# simulation.net
KiCad netlist of a schematic drawn in Altium Designer
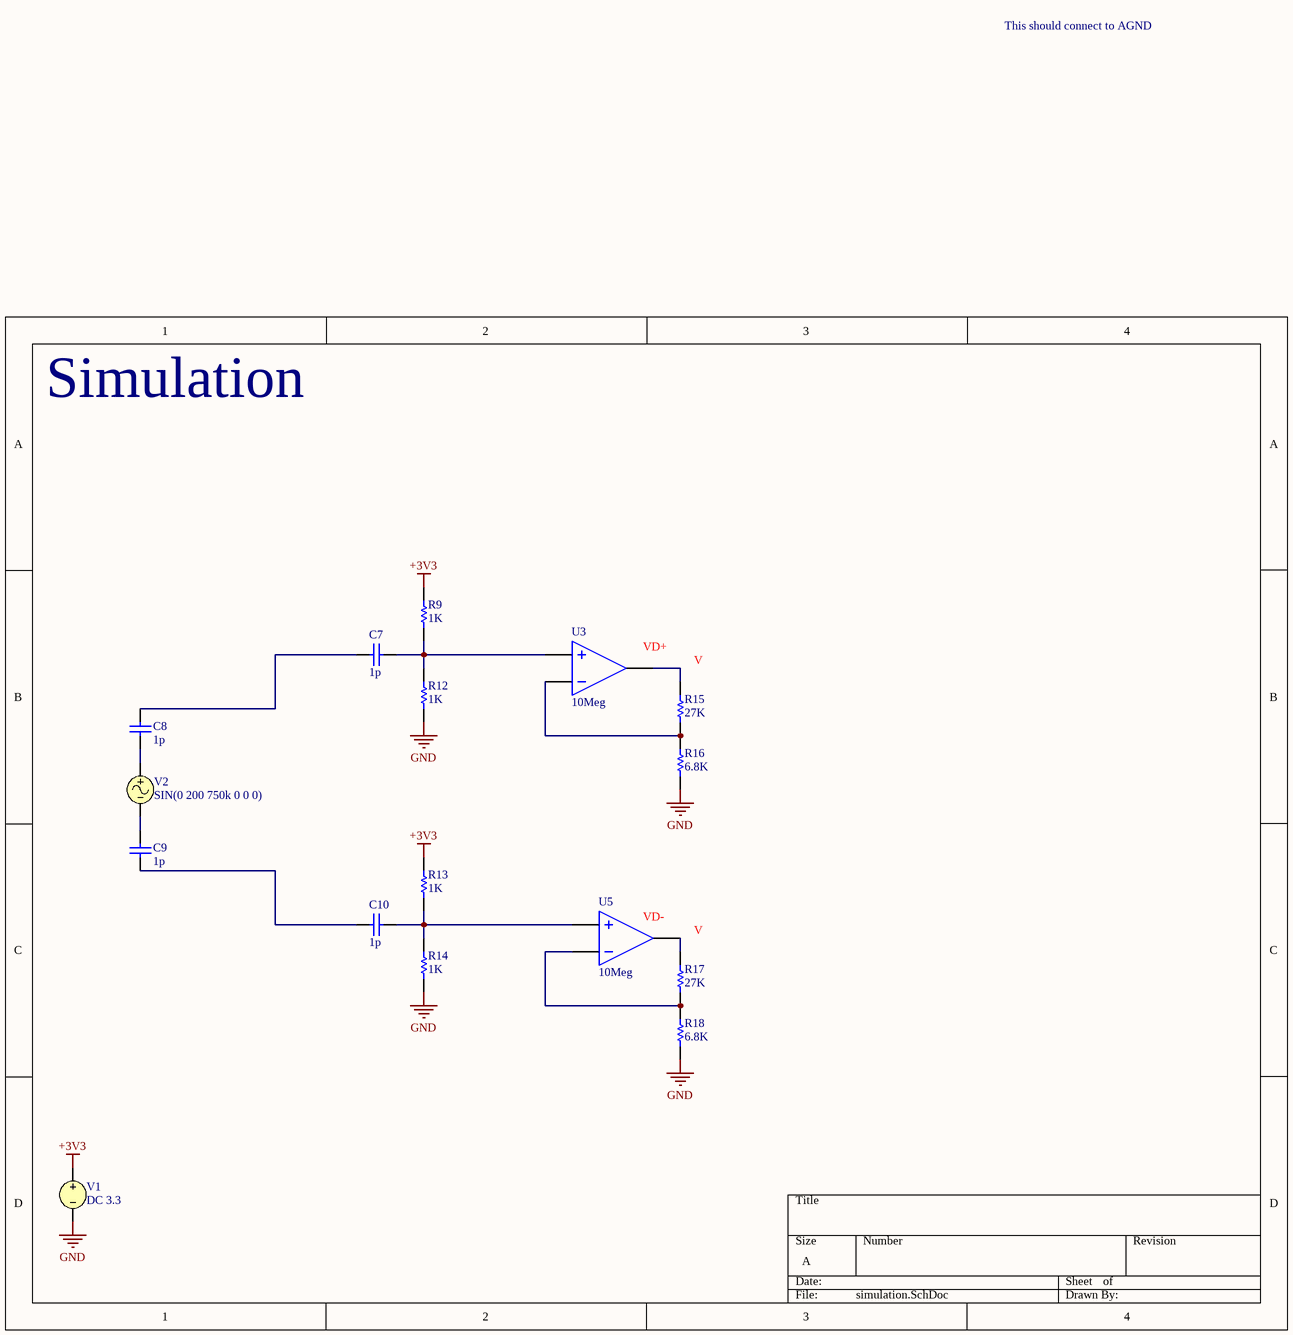
[diagram p0: simulation.SchDoc]

(export (version "E")
  (design (tool "Eeschema 10.0.6"))
  (components
    (comp (ref "C7")
      (value "1p")
      (description "Capacitor")
      (libsource (lib "Simulation Generic Components") (part "Capacitor"))
    )
    (comp (ref "C8")
      (value "1p")
      (description "Capacitor")
      (libsource (lib "Simulation Generic Components") (part "Capacitor"))
    )
    (comp (ref "C9")
      (value "1p")
      (description "Capacitor")
      (libsource (lib "Simulation Generic Components") (part "Capacitor"))
    )
    (comp (ref "C10")
      (value "1p")
      (description "Capacitor")
      (libsource (lib "Simulation Generic Components") (part "Capacitor"))
    )
    (comp (ref "R9")
      (value "1K")
      (description "Resistor")
      (libsource (lib "Simulation Generic Components") (part "Resistor"))
    )
    (comp (ref "R12")
      (value "1K")
      (description "Resistor")
      (libsource (lib "Simulation Generic Components") (part "Resistor"))
    )
    (comp (ref "R13")
      (value "1K")
      (description "Resistor")
      (libsource (lib "Simulation Generic Components") (part "Resistor"))
    )
    (comp (ref "R14")
      (value "1K")
      (description "Resistor")
      (libsource (lib "Simulation Generic Components") (part "Resistor"))
    )
    (comp (ref "R15")
      (value "27K")
      (description "Resistor")
      (libsource (lib "Simulation Generic Components") (part "Resistor"))
    )
    (comp (ref "R16")
      (value "6.8K")
      (description "Resistor")
      (libsource (lib "Simulation Generic Components") (part "Resistor"))
    )
    (comp (ref "R17")
      (value "27K")
      (description "Resistor")
      (libsource (lib "Simulation Generic Components") (part "Resistor"))
    )
    (comp (ref "R18")
      (value "6.8K")
      (description "Resistor")
      (libsource (lib "Simulation Generic Components") (part "Resistor"))
    )
    (comp (ref "U3")
      (value "Ideal Operational Amplifier")
      (fields (field (name "GAIN") "10Meg"))
      (libsource (lib "Simulation Generic Components") (part "OpAmp"))
    )
    (comp (ref "U5")
      (value "Ideal Operational Amplifier")
      (fields (field (name "GAIN") "10Meg"))
      (libsource (lib "Simulation Generic Components") (part "OpAmp"))
    )
    (comp (ref "V1")
      (value "DC 3.3")
      (description "Voltage Source")
      (fields (field (name "PUBLISHER") "Altium Limited"))
      (libsource (lib "Simulation Generic Components") (part "VSRC"))
    )
    (comp (ref "V2")
      (value "SIN(0 200 750k 0 0 0)")
      (description "Sinusoidal Voltage Source")
      (fields (field (name "PUBLISHER") "Altium Limited"))
      (libsource (lib "Simulation Generic Components") (part "VSIN"))
    )
  )
  (nets
    (net (code "1") (name "+3V3") (class "Default")
      (node (ref "R13") (pin "2") (pinfunction "2_2") (pintype "passive"))
      (node (ref "R9") (pin "2") (pinfunction "2_2") (pintype "passive"))
      (node (ref "V1") (pin "1") (pinfunction "1_1") (pintype "passive"))
    )
    (net (code "2") (name "GND") (class "Default")
      (node (ref "R12") (pin "1") (pinfunction "1_1") (pintype "passive"))
      (node (ref "R14") (pin "1") (pinfunction "1_1") (pintype "passive"))
      (node (ref "R16") (pin "1") (pinfunction "1_1") (pintype "passive"))
      (node (ref "R18") (pin "1") (pinfunction "1_1") (pintype "passive"))
      (node (ref "V1") (pin "2") (pinfunction "2_2") (pintype "passive"))
    )
    (net (code "3") (name "Net-(C7-Pad1)") (class "Default")
      (node (ref "C7") (pin "1") (pinfunction "1_1") (pintype "passive"))
      (node (ref "C8") (pin "2") (pinfunction "2_2") (pintype "passive"))
    )
    (net (code "4") (name "Net-(C8-Pad1)") (class "Default")
      (node (ref "C8") (pin "1") (pinfunction "1_1") (pintype "passive"))
      (node (ref "V2") (pin "1") (pinfunction "1_1") (pintype "passive"))
    )
    (net (code "5") (name "Net-(C9-Pad2)") (class "Default")
      (node (ref "C9") (pin "2") (pinfunction "2_2") (pintype "passive"))
      (node (ref "V2") (pin "2") (pinfunction "2_2") (pintype "passive"))
    )
    (net (code "6") (name "Net-(C10-Pad1)") (class "Default")
      (node (ref "C10") (pin "1") (pinfunction "1_1") (pintype "passive"))
      (node (ref "C9") (pin "1") (pinfunction "1_1") (pintype "passive"))
    )
    (net (code "7") (name "Net-(U3-IN+)") (class "Default")
      (node (ref "C7") (pin "2") (pinfunction "2_2") (pintype "passive"))
      (node (ref "R12") (pin "2") (pinfunction "2_2") (pintype "passive"))
      (node (ref "R9") (pin "1") (pinfunction "1_1") (pintype "passive"))
      (node (ref "U3") (pin "2") (pinfunction "IN+_2") (pintype "passive"))
    )
    (net (code "8") (name "Net-(U3-IN-)") (class "Default")
      (node (ref "R15") (pin "1") (pinfunction "1_1") (pintype "passive"))
      (node (ref "R16") (pin "2") (pinfunction "2_2") (pintype "passive"))
      (node (ref "U3") (pin "1") (pinfunction "IN-_1") (pintype "passive"))
    )
    (net (code "9") (name "Net-(U3-OUT)") (class "Default")
      (node (ref "R15") (pin "2") (pinfunction "2_2") (pintype "passive"))
      (node (ref "U3") (pin "3") (pinfunction "OUT_3") (pintype "passive"))
    )
    (net (code "10") (name "Net-(U5-IN+)") (class "Default")
      (node (ref "C10") (pin "2") (pinfunction "2_2") (pintype "passive"))
      (node (ref "R13") (pin "1") (pinfunction "1_1") (pintype "passive"))
      (node (ref "R14") (pin "2") (pinfunction "2_2") (pintype "passive"))
      (node (ref "U5") (pin "2") (pinfunction "IN+_2") (pintype "passive"))
    )
    (net (code "11") (name "Net-(U5-IN-)") (class "Default")
      (node (ref "R17") (pin "1") (pinfunction "1_1") (pintype "passive"))
      (node (ref "R18") (pin "2") (pinfunction "2_2") (pintype "passive"))
      (node (ref "U5") (pin "1") (pinfunction "IN-_1") (pintype "passive"))
    )
    (net (code "12") (name "Net-(U5-OUT)") (class "Default")
      (node (ref "R17") (pin "2") (pinfunction "2_2") (pintype "passive"))
      (node (ref "U5") (pin "3") (pinfunction "OUT_3") (pintype "passive"))
    )
  )
)
